# Xbee.net
KiCad netlist of a schematic drawn in Altium Designer
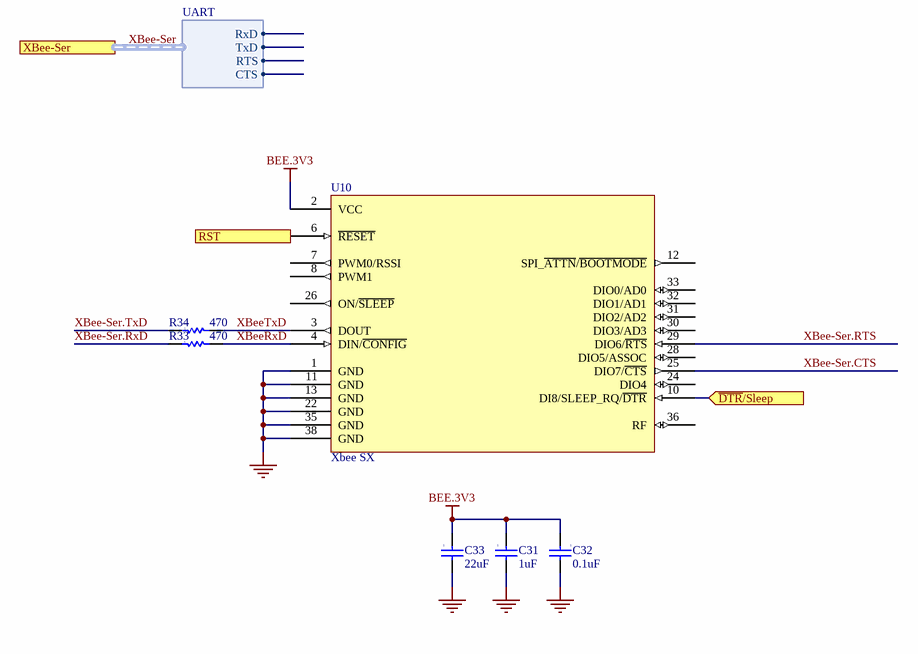
[diagram p0: Xbee.SchDoc]

(export (version "E")
  (design (tool "Eeschema 10.0.6"))
  (components
    (comp (ref "C31")
      (value "1uF")
      (footprint "0603")
      (description "CAP CER 1UF 25V X7R 0603")
      (fields
        (field (name "MANUFACTURER") "Samsung")
        (field (name "MANUFACTURER PART NUMBER") "CL10B105KA8NNNC")
        (field (name "PUBLISHER") "Altium Limited")
      )
      (libsource (lib "General") (part "Cap"))
    )
    (comp (ref "C32")
      (value "0.1uF")
      (footprint "0402")
      (description "CAP CER .10UF 50V X7R 10% 0402")
      (fields
        (field (name "MANUFACTURER") "TDK Corporation")
        (field (name "MANUFACTURER PART NUMBER") "C1005X7R1H104K")
        (field (name "PUBLISHER") "Altium Limited")
      )
      (libsource (lib "") (part "Cap_1"))
    )
    (comp (ref "C33")
      (value "22uF")
      (footprint "1206")
      (description "CAP CER 22UF 10V X5R 1206")
      (fields
        (field (name "MANUFACTURER") "Samsung")
        (field (name "MANUFACTURER PART NUMBER") "CL31A226KPHNNNE")
      )
      (libsource (lib "General") (part "Cap"))
    )
    (comp (ref "R33")
      (value "470")
      (footprint "R0402")
      (description "RES 470 OHM 1/16W 1% 0402 SMD")
      (fields
        (field (name "MANUFACTURER") "Vishay Dale")
        (field (name "MANUFACTURER PART NUMBER") "CRCW0402470RFKED")
      )
      (libsource (lib "General") (part "Res"))
    )
    (comp (ref "R34")
      (value "470")
      (footprint "R0402")
      (description "RES 470 OHM 1/16W 1% 0402 SMD")
      (fields
        (field (name "MANUFACTURER") "Vishay Dale")
        (field (name "MANUFACTURER PART NUMBER") "CRCW0402470RFKED")
      )
      (libsource (lib "General") (part "Res"))
    )
    (comp (ref "U10")
      (value "Xbee SX")
      (footprint "XBP9X-DMUS-001")
      (description "XBEE PRO MOD TXRX ISM 915MHZ UFL")
      (fields
        (field (name "MANUFACTURER") "Digi International")
        (field (name "MANUFACTURER PART NUMBER") "XBP9X-DMUS-001")
      )
      (libsource (lib "General") (part "Xbee SX"))
    )
  )
  (nets
    (net (code "2") (name "/RST") (class "Default")
      (node (ref "U10") (pin "6") (pinfunction "~{RESET}_6") (pintype "input"))
    )
    (net (code "3") (name "/XBee-Ser.CTS") (class "Default")
      (node (ref "U10") (pin "25") (pinfunction "DIO7/~{CTS}_25") (pintype "output"))
    )
    (net (code "4") (name "/XBee-Ser.RTS") (class "Default")
      (node (ref "U10") (pin "29") (pinfunction "DIO6/~{RTS}_29") (pintype "input"))
    )
    (net (code "5") (name "/XBee-Ser.RxD") (class "Default")
      (node (ref "R33") (pin "1") (pinfunction "1_1") (pintype "passive"))
    )
    (net (code "6") (name "/XBee-Ser.TxD") (class "Default")
      (node (ref "R34") (pin "1") (pinfunction "1_1") (pintype "passive"))
    )
    (net (code "8") (name "/XBeeRxD") (class "Default")
      (node (ref "R33") (pin "2") (pinfunction "2_2") (pintype "passive"))
      (node (ref "U10") (pin "4") (pinfunction "DIN/~{CONFIG}_4") (pintype "input"))
    )
    (net (code "9") (name "/XBeeTxD") (class "Default")
      (node (ref "R34") (pin "2") (pinfunction "2_2") (pintype "passive"))
      (node (ref "U10") (pin "3") (pinfunction "DOUT_3") (pintype "output"))
    )
    (net (code "10") (name "/~{DTR}{slash}Sleep") (class "Default")
      (node (ref "U10") (pin "10") (pinfunction "DI8/SLEEP_RQ/~{DTR}_10") (pintype "input"))
    )
    (net (code "11") (name "BEE.3V3") (class "Default")
      (node (ref "C31") (pin "1") (pinfunction "1_1") (pintype "passive"))
      (node (ref "C32") (pin "1") (pinfunction "1_1") (pintype "passive"))
      (node (ref "C33") (pin "1") (pinfunction "1_1") (pintype "passive"))
      (node (ref "U10") (pin "2") (pinfunction "VCC_2") (pintype "power_in"))
    )
    (net (code "12") (name "GND") (class "Default")
      (node (ref "C31") (pin "2") (pinfunction "2_2") (pintype "passive"))
      (node (ref "C32") (pin "2") (pinfunction "2_2") (pintype "passive"))
      (node (ref "C33") (pin "2") (pinfunction "2_2") (pintype "passive"))
      (node (ref "U10") (pin "1") (pinfunction "GND_1") (pintype "power_in"))
      (node (ref "U10") (pin "11") (pinfunction "GND_11") (pintype "power_in"))
      (node (ref "U10") (pin "13") (pinfunction "GND_13") (pintype "power_in"))
      (node (ref "U10") (pin "22") (pinfunction "GND_22") (pintype "power_in"))
      (node (ref "U10") (pin "35") (pinfunction "GND_35") (pintype "power_in"))
      (node (ref "U10") (pin "38") (pinfunction "GND_38") (pintype "power_in"))
    )
    (net (code "13") (name "unconnected-(U10-DIO0{slash}AD0-Pad33)") (class "Default")
      (node (ref "U10") (pin "33") (pinfunction "DIO0/AD0_33") (pintype "bidirectional"))
    )
    (net (code "14") (name "unconnected-(U10-DIO1{slash}AD1-Pad32)") (class "Default")
      (node (ref "U10") (pin "32") (pinfunction "DIO1/AD1_32") (pintype "bidirectional"))
    )
    (net (code "15") (name "unconnected-(U10-DIO2{slash}AD2-Pad31)") (class "Default")
      (node (ref "U10") (pin "31") (pinfunction "DIO2/AD2_31") (pintype "bidirectional"))
    )
    (net (code "16") (name "unconnected-(U10-DIO3{slash}AD3-Pad30)") (class "Default")
      (node (ref "U10") (pin "30") (pinfunction "DIO3/AD3_30") (pintype "bidirectional"))
    )
    (net (code "17") (name "unconnected-(U10-DIO4-Pad24)") (class "Default")
      (node (ref "U10") (pin "24") (pinfunction "DIO4_24") (pintype "bidirectional"))
    )
    (net (code "18") (name "unconnected-(U10-DIO5{slash}ASSOC-Pad28)") (class "Default")
      (node (ref "U10") (pin "28") (pinfunction "DIO5/ASSOC_28") (pintype "bidirectional"))
    )
    (net (code "19") (name "unconnected-(U10-ON{slash}~{SLEEP}-Pad26)") (class "Default")
      (node (ref "U10") (pin "26") (pinfunction "ON/~{SLEEP}_26") (pintype "output"))
    )
    (net (code "20") (name "unconnected-(U10-PWM0{slash}RSSI-Pad7)") (class "Default")
      (node (ref "U10") (pin "7") (pinfunction "PWM0/RSSI_7") (pintype "output"))
    )
    (net (code "21") (name "unconnected-(U10-PWM1-Pad8)") (class "Default")
      (node (ref "U10") (pin "8") (pinfunction "PWM1_8") (pintype "output"))
    )
    (net (code "22") (name "unconnected-(U10-RF-Pad36)") (class "Default")
      (node (ref "U10") (pin "36") (pinfunction "RF_36") (pintype "bidirectional"))
    )
    (net (code "23") (name "unconnected-(U10-SPI_~{ATTN}{slash}~{BOOTMODE}-Pad12)") (class "Default")
      (node (ref "U10") (pin "12") (pinfunction "SPI_~{ATTN}/~{BOOTMODE}_12") (pintype "output"))
    )
  )
)
